# FPGA_Power_GND.net
KiCad netlist of a schematic drawn in Altium Designer
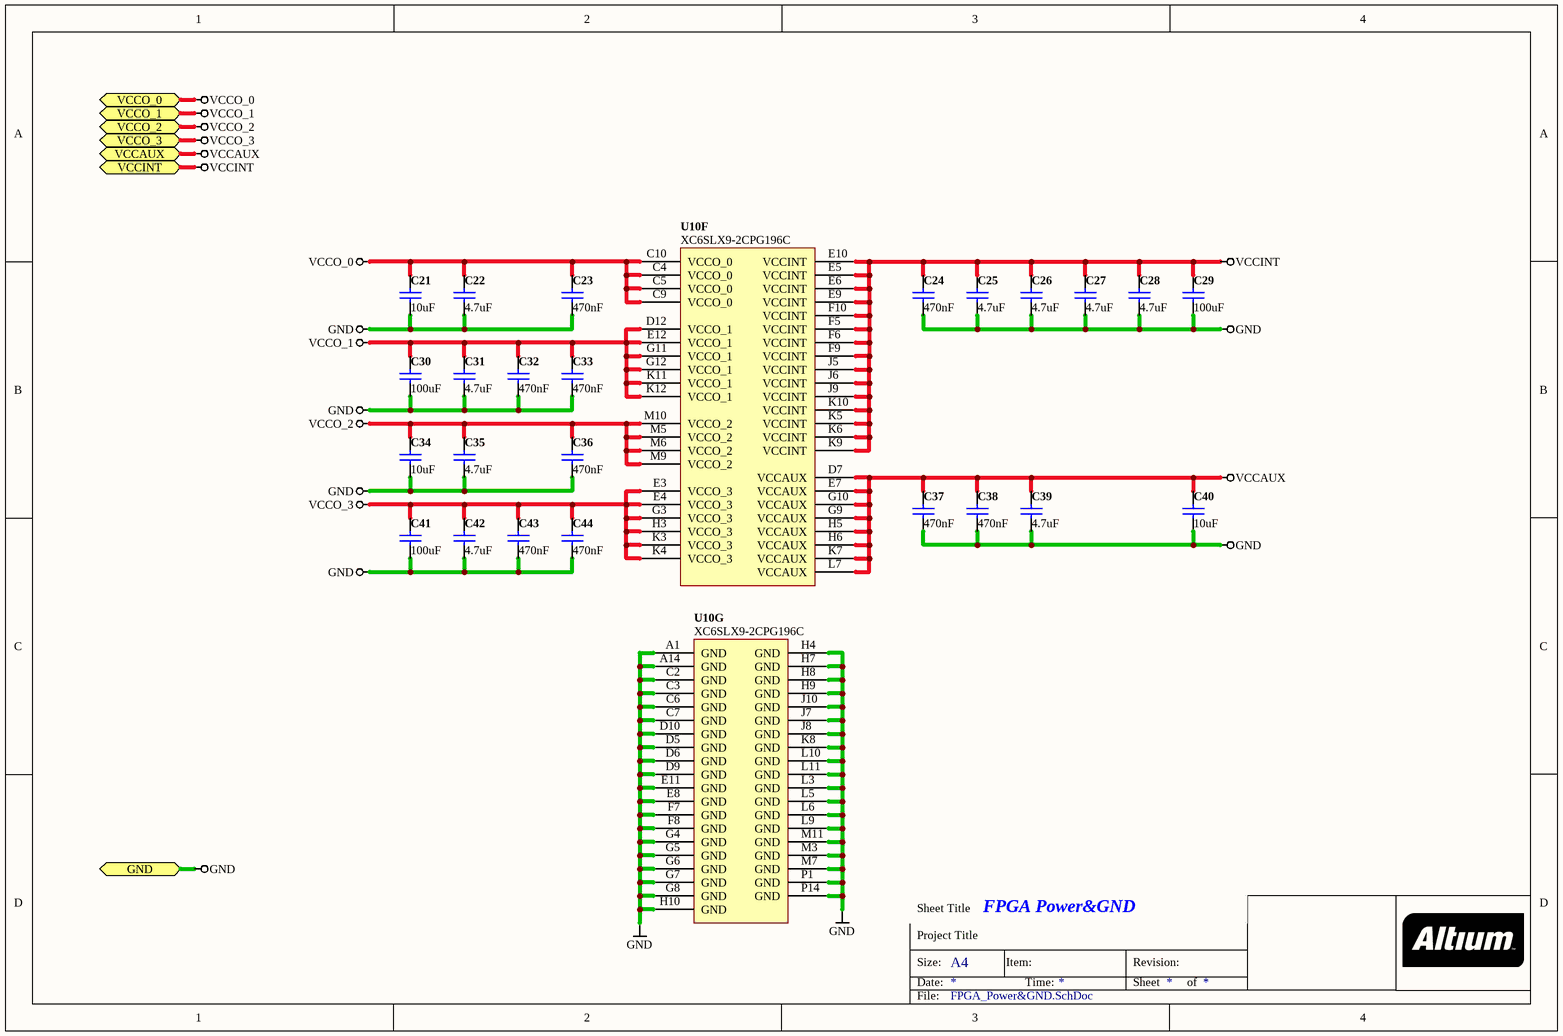
[diagram p0: FPGA_Power&GND.SchDoc]

(export (version "E")
  (design (tool "Eeschema 10.0.6"))
  (components
    (comp (ref "C21")
      (value "10uF")
      (footprint "CAPC0603(1608)100_N")
      (description "CAP 10uF 6.3V ?0% 0603 (1608 Metric) Thickness 1mm SMD")
      (fields (field (name "TOLERANCE") "?0%") (field (name "Comment") "CAP 10uF 6.3V 0603(1608)"))
      (libsource (lib "Altium Content Vault") (part "CMP-1035-02797-1"))
    )
    (comp (ref "C22")
      (value "4.7uF")
      (footprint "CAPC0402(1005)60_N")
      (description "CAP 4.7uF 6.3V ?0% 0402 (1005 Metric) Thickness 0.6mm SMD")
      (fields (field (name "TOLERANCE") "?0%") (field (name "Comment") "CAP 4.7uF 6.3V 0402(1005)"))
      (libsource (lib "Altium Content Vault") (part "CMP-1034-02137-1"))
    )
    (comp (ref "C23")
      (value "470nF")
      (footprint "CAPC0402(1005)60_N")
      (description "CAP 470nF 6.3V ?0% 0402 (1005 Metric) Thickness 0.6mm SMD")
      (fields (field (name "TOLERANCE") "?0%") (field (name "Comment") "CAP 470nF 6.3V 0402(1005)"))
      (libsource (lib "Altium Content Vault") (part "CMP-1034-02104-1"))
    )
    (comp (ref "C24")
      (value "470nF")
      (footprint "CAPC0402(1005)60_N")
      (description "CAP 470nF 6.3V ?0% 0402 (1005 Metric) Thickness 0.6mm SMD")
      (fields (field (name "TOLERANCE") "?0%") (field (name "Comment") "CAP 470nF 6.3V 0402(1005)"))
      (libsource (lib "Altium Content Vault") (part "CMP-1034-02104-1"))
    )
    (comp (ref "C25")
      (value "4.7uF")
      (footprint "CAPC0402(1005)60_N")
      (description "CAP 4.7uF 6.3V ?0% 0402 (1005 Metric) Thickness 0.6mm SMD")
      (fields (field (name "TOLERANCE") "?0%") (field (name "Comment") "CAP 4.7uF 6.3V 0402(1005)"))
      (libsource (lib "Altium Content Vault") (part "CMP-1034-02137-1"))
    )
    (comp (ref "C26")
      (value "4.7uF")
      (footprint "CAPC0402(1005)60_N")
      (description "CAP 4.7uF 6.3V ?0% 0402 (1005 Metric) Thickness 0.6mm SMD")
      (fields (field (name "TOLERANCE") "?0%") (field (name "Comment") "CAP 4.7uF 6.3V 0402(1005)"))
      (libsource (lib "Altium Content Vault") (part "CMP-1034-02137-1"))
    )
    (comp (ref "C27")
      (value "4.7uF")
      (footprint "CAPC0402(1005)60_N")
      (description "CAP 4.7uF 6.3V ?0% 0402 (1005 Metric) Thickness 0.6mm SMD")
      (fields (field (name "TOLERANCE") "?0%") (field (name "Comment") "CAP 4.7uF 6.3V 0402(1005)"))
      (libsource (lib "Altium Content Vault") (part "CMP-1034-02137-1"))
    )
    (comp (ref "C28")
      (value "4.7uF")
      (footprint "CAPC0402(1005)60_N")
      (description "CAP 4.7uF 6.3V ?0% 0402 (1005 Metric) Thickness 0.6mm SMD")
      (fields (field (name "TOLERANCE") "?0%") (field (name "Comment") "CAP 4.7uF 6.3V 0402(1005)"))
      (libsource (lib "Altium Content Vault") (part "CMP-1034-02137-1"))
    )
    (comp (ref "C29")
      (value "100uF")
      (footprint "CAPC1206(3216)190_L")
      (description "CAP 100uF 6.3V ?0% 1206 (3216 Metric) Thickness 1.9mm SMD")
      (fields (field (name "TOLERANCE") "?0%") (field (name "Comment") "CAP 100uF 6.3V 1206(3216)"))
      (libsource (lib "Altium Content Vault") (part "CMP-1037-05005-1"))
    )
    (comp (ref "C30")
      (value "100uF")
      (footprint "CAPC1206(3216)190_L")
      (description "CAP 100uF 6.3V ?0% 1206 (3216 Metric) Thickness 1.9mm SMD")
      (fields (field (name "TOLERANCE") "?0%") (field (name "Comment") "CAP 100uF 6.3V 1206(3216)"))
      (libsource (lib "Altium Content Vault") (part "CMP-1037-05005-1"))
    )
    (comp (ref "C31")
      (value "4.7uF")
      (footprint "CAPC0402(1005)60_N")
      (description "CAP 4.7uF 6.3V ?0% 0402 (1005 Metric) Thickness 0.6mm SMD")
      (fields (field (name "TOLERANCE") "?0%") (field (name "Comment") "CAP 4.7uF 6.3V 0402(1005)"))
      (libsource (lib "Altium Content Vault") (part "CMP-1034-02137-1"))
    )
    (comp (ref "C32")
      (value "470nF")
      (footprint "CAPC0402(1005)60_N")
      (description "CAP 470nF 6.3V ?0% 0402 (1005 Metric) Thickness 0.6mm SMD")
      (fields (field (name "TOLERANCE") "?0%") (field (name "Comment") "CAP 470nF 6.3V 0402(1005)"))
      (libsource (lib "Altium Content Vault") (part "CMP-1034-02104-1"))
    )
    (comp (ref "C33")
      (value "470nF")
      (footprint "CAPC0402(1005)60_N")
      (description "CAP 470nF 6.3V ?0% 0402 (1005 Metric) Thickness 0.6mm SMD")
      (fields (field (name "TOLERANCE") "?0%") (field (name "Comment") "CAP 470nF 6.3V 0402(1005)"))
      (libsource (lib "Altium Content Vault") (part "CMP-1034-02104-1"))
    )
    (comp (ref "C34")
      (value "10uF")
      (footprint "CAPC0603(1608)100_N")
      (description "CAP 10uF 6.3V ?0% 0603 (1608 Metric) Thickness 1mm SMD")
      (fields (field (name "TOLERANCE") "?0%") (field (name "Comment") "CAP 10uF 6.3V 0603(1608)"))
      (libsource (lib "Altium Content Vault") (part "CMP-1035-02797-1"))
    )
    (comp (ref "C35")
      (value "4.7uF")
      (footprint "CAPC0402(1005)60_N")
      (description "CAP 4.7uF 6.3V ?0% 0402 (1005 Metric) Thickness 0.6mm SMD")
      (fields (field (name "TOLERANCE") "?0%") (field (name "Comment") "CAP 4.7uF 6.3V 0402(1005)"))
      (libsource (lib "Altium Content Vault") (part "CMP-1034-02137-1"))
    )
    (comp (ref "C36")
      (value "470nF")
      (footprint "CAPC0402(1005)60_N")
      (description "CAP 470nF 6.3V ?0% 0402 (1005 Metric) Thickness 0.6mm SMD")
      (fields (field (name "TOLERANCE") "?0%") (field (name "Comment") "CAP 470nF 6.3V 0402(1005)"))
      (libsource (lib "Altium Content Vault") (part "CMP-1034-02104-1"))
    )
    (comp (ref "C37")
      (value "470nF")
      (footprint "CAPC0402(1005)60_N")
      (description "CAP 470nF 6.3V ?0% 0402 (1005 Metric) Thickness 0.6mm SMD")
      (fields (field (name "TOLERANCE") "?0%") (field (name "Comment") "CAP 470nF 6.3V 0402(1005)"))
      (libsource (lib "Altium Content Vault") (part "CMP-1034-02104-1"))
    )
    (comp (ref "C38")
      (value "470nF")
      (footprint "CAPC0402(1005)60_N")
      (description "CAP 470nF 6.3V ?0% 0402 (1005 Metric) Thickness 0.6mm SMD")
      (fields (field (name "TOLERANCE") "?0%") (field (name "Comment") "CAP 470nF 6.3V 0402(1005)"))
      (libsource (lib "Altium Content Vault") (part "CMP-1034-02104-1"))
    )
    (comp (ref "C39")
      (value "4.7uF")
      (footprint "CAPC0402(1005)60_N")
      (description "CAP 4.7uF 6.3V ?0% 0402 (1005 Metric) Thickness 0.6mm SMD")
      (fields (field (name "TOLERANCE") "?0%") (field (name "Comment") "CAP 4.7uF 6.3V 0402(1005)"))
      (libsource (lib "Altium Content Vault") (part "CMP-1034-02137-1"))
    )
    (comp (ref "C40")
      (value "10uF")
      (footprint "CAPC0603(1608)100_N")
      (description "CAP 10uF 6.3V ?0% 0603 (1608 Metric) Thickness 1mm SMD")
      (fields (field (name "TOLERANCE") "?0%") (field (name "Comment") "CAP 10uF 6.3V 0603(1608)"))
      (libsource (lib "Altium Content Vault") (part "CMP-1035-02797-1"))
    )
    (comp (ref "C41")
      (value "100uF")
      (footprint "CAPC1206(3216)190_L")
      (description "CAP 100uF 6.3V ?0% 1206 (3216 Metric) Thickness 1.9mm SMD")
      (fields (field (name "TOLERANCE") "?0%") (field (name "Comment") "CAP 100uF 6.3V 1206(3216)"))
      (libsource (lib "Altium Content Vault") (part "CMP-1037-05005-1"))
    )
    (comp (ref "C42")
      (value "4.7uF")
      (footprint "CAPC0402(1005)60_N")
      (description "CAP 4.7uF 6.3V ?0% 0402 (1005 Metric) Thickness 0.6mm SMD")
      (fields (field (name "TOLERANCE") "?0%") (field (name "Comment") "CAP 4.7uF 6.3V 0402(1005)"))
      (libsource (lib "Altium Content Vault") (part "CMP-1034-02137-1"))
    )
    (comp (ref "C43")
      (value "470nF")
      (footprint "CAPC0402(1005)60_N")
      (description "CAP 470nF 6.3V ?0% 0402 (1005 Metric) Thickness 0.6mm SMD")
      (fields (field (name "TOLERANCE") "?0%") (field (name "Comment") "CAP 470nF 6.3V 0402(1005)"))
      (libsource (lib "Altium Content Vault") (part "CMP-1034-02104-1"))
    )
    (comp (ref "C44")
      (value "470nF")
      (footprint "CAPC0402(1005)60_N")
      (description "CAP 470nF 6.3V ?0% 0402 (1005 Metric) Thickness 0.6mm SMD")
      (fields (field (name "TOLERANCE") "?0%") (field (name "Comment") "CAP 470nF 6.3V 0402(1005)"))
      (libsource (lib "Altium Content Vault") (part "CMP-1034-02104-1"))
    )
    (comp (ref "U10")
      (value "XC6SLX9-2CPG196C")
      (footprint "CPG196")
      (libsource (lib "Altium Content Vault") (part "FPGA-XSP6-XC6SLX9-GA196"))
    )
  )
  (nets
    (net (code "1") (name "GND") (class "Default")
      (node (ref "C21") (pin "1") (pinfunction "1_1") (pintype "passive"))
      (node (ref "C22") (pin "2") (pinfunction "2_2") (pintype "passive"))
      (node (ref "C23") (pin "1") (pinfunction "1_1") (pintype "passive"))
      (node (ref "C24") (pin "1") (pinfunction "1_1") (pintype "passive"))
      (node (ref "C25") (pin "1") (pinfunction "1_1") (pintype "passive"))
      (node (ref "C26") (pin "1") (pinfunction "1_1") (pintype "passive"))
      (node (ref "C27") (pin "1") (pinfunction "1_1") (pintype "passive"))
      (node (ref "C28") (pin "2") (pinfunction "2_2") (pintype "passive"))
      (node (ref "C29") (pin "1") (pinfunction "1_1") (pintype "passive"))
      (node (ref "C30") (pin "1") (pinfunction "1_1") (pintype "passive"))
      (node (ref "C31") (pin "1") (pinfunction "1_1") (pintype "passive"))
      (node (ref "C32") (pin "1") (pinfunction "1_1") (pintype "passive"))
      (node (ref "C33") (pin "1") (pinfunction "1_1") (pintype "passive"))
      (node (ref "C34") (pin "1") (pinfunction "1_1") (pintype "passive"))
      (node (ref "C35") (pin "2") (pinfunction "2_2") (pintype "passive"))
      (node (ref "C36") (pin "1") (pinfunction "1_1") (pintype "passive"))
      (node (ref "C37") (pin "1") (pinfunction "1_1") (pintype "passive"))
      (node (ref "C38") (pin "1") (pinfunction "1_1") (pintype "passive"))
      (node (ref "C39") (pin "2") (pinfunction "2_2") (pintype "passive"))
      (node (ref "C40") (pin "1") (pinfunction "1_1") (pintype "passive"))
      (node (ref "C41") (pin "2") (pinfunction "2_2") (pintype "passive"))
      (node (ref "C42") (pin "1") (pinfunction "1_1") (pintype "passive"))
      (node (ref "C43") (pin "1") (pinfunction "1_1") (pintype "passive"))
      (node (ref "C44") (pin "1") (pinfunction "1_1") (pintype "passive"))
      (node (ref "U10") (pin "A1") (pinfunction "GND_A1") (pintype "power_in"))
      (node (ref "U10") (pin "A14") (pinfunction "GND_A14") (pintype "power_in"))
      (node (ref "U10") (pin "C2") (pinfunction "GND_C2") (pintype "power_in"))
      (node (ref "U10") (pin "C3") (pinfunction "GND_C3") (pintype "power_in"))
      (node (ref "U10") (pin "C6") (pinfunction "GND_C6") (pintype "power_in"))
      (node (ref "U10") (pin "C7") (pinfunction "GND_C7") (pintype "power_in"))
      (node (ref "U10") (pin "D10") (pinfunction "GND_D10") (pintype "power_in"))
      (node (ref "U10") (pin "D5") (pinfunction "GND_D5") (pintype "power_in"))
      (node (ref "U10") (pin "D6") (pinfunction "GND_D6") (pintype "power_in"))
      (node (ref "U10") (pin "D9") (pinfunction "GND_D9") (pintype "power_in"))
      (node (ref "U10") (pin "E11") (pinfunction "GND_E11") (pintype "power_in"))
      (node (ref "U10") (pin "E8") (pinfunction "GND_E8") (pintype "power_in"))
      (node (ref "U10") (pin "F7") (pinfunction "GND_F7") (pintype "power_in"))
      (node (ref "U10") (pin "F8") (pinfunction "GND_F8") (pintype "power_in"))
      (node (ref "U10") (pin "G4") (pinfunction "GND_G4") (pintype "power_in"))
      (node (ref "U10") (pin "G5") (pinfunction "GND_G5") (pintype "power_in"))
      (node (ref "U10") (pin "G6") (pinfunction "GND_G6") (pintype "power_in"))
      (node (ref "U10") (pin "G7") (pinfunction "GND_G7") (pintype "power_in"))
      (node (ref "U10") (pin "G8") (pinfunction "GND_G8") (pintype "power_in"))
      (node (ref "U10") (pin "H10") (pinfunction "GND_H10") (pintype "power_in"))
      (node (ref "U10") (pin "H4") (pinfunction "GND_H4") (pintype "power_in"))
      (node (ref "U10") (pin "H7") (pinfunction "GND_H7") (pintype "power_in"))
      (node (ref "U10") (pin "H8") (pinfunction "GND_H8") (pintype "power_in"))
      (node (ref "U10") (pin "H9") (pinfunction "GND_H9") (pintype "power_in"))
      (node (ref "U10") (pin "J10") (pinfunction "GND_J10") (pintype "power_in"))
      (node (ref "U10") (pin "J7") (pinfunction "GND_J7") (pintype "power_in"))
      (node (ref "U10") (pin "J8") (pinfunction "GND_J8") (pintype "power_in"))
      (node (ref "U10") (pin "K8") (pinfunction "GND_K8") (pintype "power_in"))
      (node (ref "U10") (pin "L10") (pinfunction "GND_L10") (pintype "power_in"))
      (node (ref "U10") (pin "L11") (pinfunction "GND_L11") (pintype "power_in"))
      (node (ref "U10") (pin "L3") (pinfunction "GND_L3") (pintype "power_in"))
      (node (ref "U10") (pin "L5") (pinfunction "GND_L5") (pintype "power_in"))
      (node (ref "U10") (pin "L6") (pinfunction "GND_L6") (pintype "power_in"))
      (node (ref "U10") (pin "L9") (pinfunction "GND_L9") (pintype "power_in"))
      (node (ref "U10") (pin "M11") (pinfunction "GND_M11") (pintype "power_in"))
      (node (ref "U10") (pin "M3") (pinfunction "GND_M3") (pintype "power_in"))
      (node (ref "U10") (pin "M7") (pinfunction "GND_M7") (pintype "power_in"))
      (node (ref "U10") (pin "P1") (pinfunction "GND_P1") (pintype "power_in"))
      (node (ref "U10") (pin "P14") (pinfunction "GND_P14") (pintype "power_in"))
    )
    (net (code "2") (name "VCCAUX") (class "Default")
      (node (ref "C37") (pin "2") (pinfunction "2_2") (pintype "passive"))
      (node (ref "C38") (pin "2") (pinfunction "2_2") (pintype "passive"))
      (node (ref "C39") (pin "1") (pinfunction "1_1") (pintype "passive"))
      (node (ref "C40") (pin "2") (pinfunction "2_2") (pintype "passive"))
      (node (ref "U10") (pin "D7") (pinfunction "VCCAUX_D7") (pintype "power_in"))
      (node (ref "U10") (pin "E7") (pinfunction "VCCAUX_E7") (pintype "power_in"))
      (node (ref "U10") (pin "G10") (pinfunction "VCCAUX_G10") (pintype "power_in"))
      (node (ref "U10") (pin "G9") (pinfunction "VCCAUX_G9") (pintype "power_in"))
      (node (ref "U10") (pin "H5") (pinfunction "VCCAUX_H5") (pintype "power_in"))
      (node (ref "U10") (pin "H6") (pinfunction "VCCAUX_H6") (pintype "power_in"))
      (node (ref "U10") (pin "K7") (pinfunction "VCCAUX_K7") (pintype "power_in"))
      (node (ref "U10") (pin "L7") (pinfunction "VCCAUX_L7") (pintype "power_in"))
    )
    (net (code "3") (name "VCCINT") (class "Default")
      (node (ref "C24") (pin "2") (pinfunction "2_2") (pintype "passive"))
      (node (ref "C25") (pin "2") (pinfunction "2_2") (pintype "passive"))
      (node (ref "C26") (pin "2") (pinfunction "2_2") (pintype "passive"))
      (node (ref "C27") (pin "2") (pinfunction "2_2") (pintype "passive"))
      (node (ref "C28") (pin "1") (pinfunction "1_1") (pintype "passive"))
      (node (ref "C29") (pin "2") (pinfunction "2_2") (pintype "passive"))
      (node (ref "U10") (pin "E10") (pinfunction "VCCINT_E10") (pintype "power_in"))
      (node (ref "U10") (pin "E5") (pinfunction "VCCINT_E5") (pintype "power_in"))
      (node (ref "U10") (pin "E6") (pinfunction "VCCINT_E6") (pintype "power_in"))
      (node (ref "U10") (pin "E9") (pinfunction "VCCINT_E9") (pintype "power_in"))
      (node (ref "U10") (pin "F10") (pinfunction "VCCINT_F10") (pintype "power_in"))
      (node (ref "U10") (pin "F5") (pinfunction "VCCINT_F5") (pintype "power_in"))
      (node (ref "U10") (pin "F6") (pinfunction "VCCINT_F6") (pintype "power_in"))
      (node (ref "U10") (pin "F9") (pinfunction "VCCINT_F9") (pintype "power_in"))
      (node (ref "U10") (pin "J5") (pinfunction "VCCINT_J5") (pintype "power_in"))
      (node (ref "U10") (pin "J6") (pinfunction "VCCINT_J6") (pintype "power_in"))
      (node (ref "U10") (pin "J9") (pinfunction "VCCINT_J9") (pintype "power_in"))
      (node (ref "U10") (pin "K10") (pinfunction "VCCINT_K10") (pintype "power_in"))
      (node (ref "U10") (pin "K5") (pinfunction "VCCINT_K5") (pintype "power_in"))
      (node (ref "U10") (pin "K6") (pinfunction "VCCINT_K6") (pintype "power_in"))
      (node (ref "U10") (pin "K9") (pinfunction "VCCINT_K9") (pintype "power_in"))
    )
    (net (code "4") (name "VCCO_0") (class "Default")
      (node (ref "C21") (pin "2") (pinfunction "2_2") (pintype "passive"))
      (node (ref "C22") (pin "1") (pinfunction "1_1") (pintype "passive"))
      (node (ref "C23") (pin "2") (pinfunction "2_2") (pintype "passive"))
      (node (ref "U10") (pin "C10") (pinfunction "VCCO_0_C10") (pintype "power_in"))
      (node (ref "U10") (pin "C4") (pinfunction "VCCO_0_C4") (pintype "power_in"))
      (node (ref "U10") (pin "C5") (pinfunction "VCCO_0_C5") (pintype "power_in"))
      (node (ref "U10") (pin "C9") (pinfunction "VCCO_0_C9") (pintype "power_in"))
    )
    (net (code "5") (name "VCCO_1") (class "Default")
      (node (ref "C30") (pin "2") (pinfunction "2_2") (pintype "passive"))
      (node (ref "C31") (pin "2") (pinfunction "2_2") (pintype "passive"))
      (node (ref "C32") (pin "2") (pinfunction "2_2") (pintype "passive"))
      (node (ref "C33") (pin "2") (pinfunction "2_2") (pintype "passive"))
      (node (ref "U10") (pin "D12") (pinfunction "VCCO_1_D12") (pintype "power_in"))
      (node (ref "U10") (pin "E12") (pinfunction "VCCO_1_E12") (pintype "power_in"))
      (node (ref "U10") (pin "G11") (pinfunction "VCCO_1_G11") (pintype "power_in"))
      (node (ref "U10") (pin "G12") (pinfunction "VCCO_1_G12") (pintype "power_in"))
      (node (ref "U10") (pin "K11") (pinfunction "VCCO_1_K11") (pintype "power_in"))
      (node (ref "U10") (pin "K12") (pinfunction "VCCO_1_K12") (pintype "power_in"))
    )
    (net (code "6") (name "VCCO_2") (class "Default")
      (node (ref "C34") (pin "2") (pinfunction "2_2") (pintype "passive"))
      (node (ref "C35") (pin "1") (pinfunction "1_1") (pintype "passive"))
      (node (ref "C36") (pin "2") (pinfunction "2_2") (pintype "passive"))
      (node (ref "U10") (pin "M10") (pinfunction "VCCO_2_M10") (pintype "power_in"))
      (node (ref "U10") (pin "M5") (pinfunction "VCCO_2_M5") (pintype "power_in"))
      (node (ref "U10") (pin "M6") (pinfunction "VCCO_2_M6") (pintype "power_in"))
      (node (ref "U10") (pin "M9") (pinfunction "VCCO_2_M9") (pintype "power_in"))
    )
    (net (code "7") (name "VCCO_3") (class "Default")
      (node (ref "C41") (pin "1") (pinfunction "1_1") (pintype "passive"))
      (node (ref "C42") (pin "2") (pinfunction "2_2") (pintype "passive"))
      (node (ref "C43") (pin "2") (pinfunction "2_2") (pintype "passive"))
      (node (ref "C44") (pin "2") (pinfunction "2_2") (pintype "passive"))
      (node (ref "U10") (pin "E3") (pinfunction "VCCO_3_E3") (pintype "power_in"))
      (node (ref "U10") (pin "E4") (pinfunction "VCCO_3_E4") (pintype "power_in"))
      (node (ref "U10") (pin "G3") (pinfunction "VCCO_3_G3") (pintype "power_in"))
      (node (ref "U10") (pin "H3") (pinfunction "VCCO_3_H3") (pintype "power_in"))
      (node (ref "U10") (pin "K3") (pinfunction "VCCO_3_K3") (pintype "power_in"))
      (node (ref "U10") (pin "K4") (pinfunction "VCCO_3_K4") (pintype "power_in"))
    )
  )
)
